# riffle-proto-grove-1_3.net
KiCad netlist of a schematic drawn in EAGLE
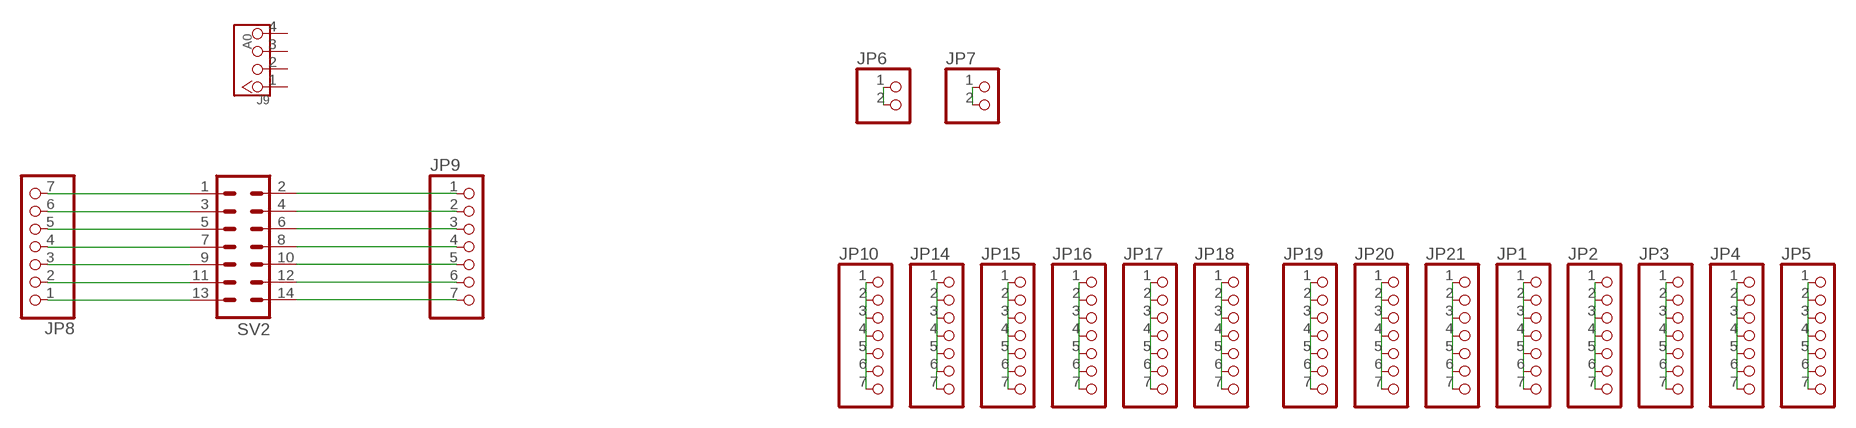
[diagram p0: schematic, sheet 1]

(export (version "E")
  (design (tool "Eeschema 10.0.6"))
  (components
    (comp (ref "J9")
      (value "A0")
      (footprint "eagle-import:4P-2.0-90D")
      (libsource (lib "eagle-import") (part "TWIG-4P-2.0'90D'"))
    )
    (comp (ref "JP1")
      (value "HEADER-1X770MIL")
      (footprint "eagle-import:1X07_ROUND_70")
      (libsource (lib "eagle-import") (part "HEADER-1X770MIL"))
    )
    (comp (ref "JP2")
      (value "HEADER-1X770MIL")
      (footprint "eagle-import:1X07_ROUND_70")
      (libsource (lib "eagle-import") (part "HEADER-1X770MIL"))
    )
    (comp (ref "JP3")
      (value "HEADER-1X770MIL")
      (footprint "eagle-import:1X07_ROUND_70")
      (libsource (lib "eagle-import") (part "HEADER-1X770MIL"))
    )
    (comp (ref "JP4")
      (value "HEADER-1X770MIL")
      (footprint "eagle-import:1X07_ROUND_70")
      (libsource (lib "eagle-import") (part "HEADER-1X770MIL"))
    )
    (comp (ref "JP5")
      (value "HEADER-1X770MIL")
      (footprint "eagle-import:1X07_ROUND_70")
      (libsource (lib "eagle-import") (part "HEADER-1X770MIL"))
    )
    (comp (ref "JP6")
      (value "HEADER-1X2ROUND")
      (footprint "eagle-import:1X02_ROUND")
      (libsource (lib "eagle-import") (part "HEADER-1X2ROUND"))
    )
    (comp (ref "JP7")
      (value "HEADER-1X2ROUND")
      (footprint "eagle-import:1X02_ROUND")
      (libsource (lib "eagle-import") (part "HEADER-1X2ROUND"))
    )
    (comp (ref "JP8")
      (value "HEADER-1X770MIL")
      (footprint "eagle-import:1X07_ROUND_70")
      (libsource (lib "eagle-import") (part "HEADER-1X770MIL"))
    )
    (comp (ref "JP9")
      (value "HEADER-1X770MIL")
      (footprint "eagle-import:1X07_ROUND_70")
      (libsource (lib "eagle-import") (part "HEADER-1X770MIL"))
    )
    (comp (ref "JP10")
      (value "HEADER-1X770MIL")
      (footprint "eagle-import:1X07_ROUND_70")
      (libsource (lib "eagle-import") (part "HEADER-1X770MIL"))
    )
    (comp (ref "JP14")
      (value "HEADER-1X770MIL")
      (footprint "eagle-import:1X07_ROUND_70")
      (libsource (lib "eagle-import") (part "HEADER-1X770MIL"))
    )
    (comp (ref "JP15")
      (value "HEADER-1X770MIL")
      (footprint "eagle-import:1X07_ROUND_70")
      (libsource (lib "eagle-import") (part "HEADER-1X770MIL"))
    )
    (comp (ref "JP16")
      (value "HEADER-1X770MIL")
      (footprint "eagle-import:1X07_ROUND_70")
      (libsource (lib "eagle-import") (part "HEADER-1X770MIL"))
    )
    (comp (ref "JP17")
      (value "HEADER-1X770MIL")
      (footprint "eagle-import:1X07_ROUND_70")
      (libsource (lib "eagle-import") (part "HEADER-1X770MIL"))
    )
    (comp (ref "JP18")
      (value "HEADER-1X770MIL")
      (footprint "eagle-import:1X07_ROUND_70")
      (libsource (lib "eagle-import") (part "HEADER-1X770MIL"))
    )
    (comp (ref "JP19")
      (value "HEADER-1X770MIL")
      (footprint "eagle-import:1X07_ROUND_70")
      (libsource (lib "eagle-import") (part "HEADER-1X770MIL"))
    )
    (comp (ref "JP20")
      (value "HEADER-1X770MIL")
      (footprint "eagle-import:1X07_ROUND_70")
      (libsource (lib "eagle-import") (part "HEADER-1X770MIL"))
    )
    (comp (ref "JP21")
      (value "HEADER-1X770MIL")
      (footprint "eagle-import:1X07_ROUND_70")
      (libsource (lib "eagle-import") (part "HEADER-1X770MIL"))
    )
    (comp (ref "SV2")
      (value "MA07-2")
      (footprint "eagle-import:MA07-2")
      (libsource (lib "eagle-import") (part "MA07-2"))
    )
  )
  (nets
    (net (code "1") (name "Net-(JP1-Pad1)") (class "Default")
      (node (ref "JP1") (pin "1") (pinfunction "1_1") (pintype "passive"))
      (node (ref "JP1") (pin "2") (pinfunction "2_2") (pintype "passive"))
      (node (ref "JP1") (pin "3") (pinfunction "3_3") (pintype "passive"))
      (node (ref "JP1") (pin "4") (pinfunction "4_4") (pintype "passive"))
      (node (ref "JP1") (pin "5") (pinfunction "5_5") (pintype "passive"))
      (node (ref "JP1") (pin "6") (pinfunction "6_6") (pintype "passive"))
      (node (ref "JP1") (pin "7") (pinfunction "7_7") (pintype "passive"))
    )
    (net (code "2") (name "Net-(JP2-Pad1)") (class "Default")
      (node (ref "JP2") (pin "1") (pinfunction "1_1") (pintype "passive"))
      (node (ref "JP2") (pin "2") (pinfunction "2_2") (pintype "passive"))
      (node (ref "JP2") (pin "3") (pinfunction "3_3") (pintype "passive"))
      (node (ref "JP2") (pin "4") (pinfunction "4_4") (pintype "passive"))
      (node (ref "JP2") (pin "5") (pinfunction "5_5") (pintype "passive"))
      (node (ref "JP2") (pin "6") (pinfunction "6_6") (pintype "passive"))
      (node (ref "JP2") (pin "7") (pinfunction "7_7") (pintype "passive"))
    )
    (net (code "3") (name "Net-(JP3-Pad1)") (class "Default")
      (node (ref "JP3") (pin "1") (pinfunction "1_1") (pintype "passive"))
      (node (ref "JP3") (pin "2") (pinfunction "2_2") (pintype "passive"))
      (node (ref "JP3") (pin "3") (pinfunction "3_3") (pintype "passive"))
      (node (ref "JP3") (pin "4") (pinfunction "4_4") (pintype "passive"))
      (node (ref "JP3") (pin "5") (pinfunction "5_5") (pintype "passive"))
      (node (ref "JP3") (pin "6") (pinfunction "6_6") (pintype "passive"))
      (node (ref "JP3") (pin "7") (pinfunction "7_7") (pintype "passive"))
    )
    (net (code "4") (name "Net-(JP4-Pad1)") (class "Default")
      (node (ref "JP4") (pin "1") (pinfunction "1_1") (pintype "passive"))
      (node (ref "JP4") (pin "2") (pinfunction "2_2") (pintype "passive"))
      (node (ref "JP4") (pin "3") (pinfunction "3_3") (pintype "passive"))
      (node (ref "JP4") (pin "4") (pinfunction "4_4") (pintype "passive"))
      (node (ref "JP4") (pin "5") (pinfunction "5_5") (pintype "passive"))
      (node (ref "JP4") (pin "6") (pinfunction "6_6") (pintype "passive"))
      (node (ref "JP4") (pin "7") (pinfunction "7_7") (pintype "passive"))
    )
    (net (code "5") (name "Net-(JP5-Pad1)") (class "Default")
      (node (ref "JP5") (pin "1") (pinfunction "1_1") (pintype "passive"))
      (node (ref "JP5") (pin "2") (pinfunction "2_2") (pintype "passive"))
      (node (ref "JP5") (pin "3") (pinfunction "3_3") (pintype "passive"))
      (node (ref "JP5") (pin "4") (pinfunction "4_4") (pintype "passive"))
      (node (ref "JP5") (pin "5") (pinfunction "5_5") (pintype "passive"))
      (node (ref "JP5") (pin "6") (pinfunction "6_6") (pintype "passive"))
      (node (ref "JP5") (pin "7") (pinfunction "7_7") (pintype "passive"))
    )
    (net (code "6") (name "Net-(JP6-Pad1)") (class "Default")
      (node (ref "JP6") (pin "1") (pinfunction "1_1") (pintype "passive"))
      (node (ref "JP6") (pin "2") (pinfunction "2_2") (pintype "passive"))
    )
    (net (code "7") (name "Net-(JP7-Pad1)") (class "Default")
      (node (ref "JP7") (pin "1") (pinfunction "1_1") (pintype "passive"))
      (node (ref "JP7") (pin "2") (pinfunction "2_2") (pintype "passive"))
    )
    (net (code "8") (name "Net-(JP8-Pad1)") (class "Default")
      (node (ref "JP8") (pin "1") (pinfunction "1_1") (pintype "passive"))
      (node (ref "SV2") (pin "13") (pinfunction "13_13") (pintype "passive"))
    )
    (net (code "9") (name "Net-(JP8-Pad2)") (class "Default")
      (node (ref "JP8") (pin "2") (pinfunction "2_2") (pintype "passive"))
      (node (ref "SV2") (pin "11") (pinfunction "11_11") (pintype "passive"))
    )
    (net (code "10") (name "Net-(JP8-Pad3)") (class "Default")
      (node (ref "JP8") (pin "3") (pinfunction "3_3") (pintype "passive"))
      (node (ref "SV2") (pin "9") (pinfunction "9_9") (pintype "passive"))
    )
    (net (code "11") (name "Net-(JP8-Pad4)") (class "Default")
      (node (ref "JP8") (pin "4") (pinfunction "4_4") (pintype "passive"))
      (node (ref "SV2") (pin "7") (pinfunction "7_7") (pintype "passive"))
    )
    (net (code "12") (name "Net-(JP8-Pad5)") (class "Default")
      (node (ref "JP8") (pin "5") (pinfunction "5_5") (pintype "passive"))
      (node (ref "SV2") (pin "5") (pinfunction "5_5") (pintype "passive"))
    )
    (net (code "13") (name "Net-(JP8-Pad6)") (class "Default")
      (node (ref "JP8") (pin "6") (pinfunction "6_6") (pintype "passive"))
      (node (ref "SV2") (pin "3") (pinfunction "3_3") (pintype "passive"))
    )
    (net (code "14") (name "Net-(JP8-Pad7)") (class "Default")
      (node (ref "JP8") (pin "7") (pinfunction "7_7") (pintype "passive"))
      (node (ref "SV2") (pin "1") (pinfunction "1_1") (pintype "passive"))
    )
    (net (code "15") (name "Net-(JP9-Pad1)") (class "Default")
      (node (ref "JP9") (pin "1") (pinfunction "1_1") (pintype "passive"))
      (node (ref "SV2") (pin "2") (pinfunction "2_2") (pintype "passive"))
    )
    (net (code "16") (name "Net-(JP9-Pad2)") (class "Default")
      (node (ref "JP9") (pin "2") (pinfunction "2_2") (pintype "passive"))
      (node (ref "SV2") (pin "4") (pinfunction "4_4") (pintype "passive"))
    )
    (net (code "17") (name "Net-(JP9-Pad3)") (class "Default")
      (node (ref "JP9") (pin "3") (pinfunction "3_3") (pintype "passive"))
      (node (ref "SV2") (pin "6") (pinfunction "6_6") (pintype "passive"))
    )
    (net (code "18") (name "Net-(JP9-Pad4)") (class "Default")
      (node (ref "JP9") (pin "4") (pinfunction "4_4") (pintype "passive"))
      (node (ref "SV2") (pin "8") (pinfunction "8_8") (pintype "passive"))
    )
    (net (code "19") (name "Net-(JP9-Pad5)") (class "Default")
      (node (ref "JP9") (pin "5") (pinfunction "5_5") (pintype "passive"))
      (node (ref "SV2") (pin "10") (pinfunction "10_10") (pintype "passive"))
    )
    (net (code "20") (name "Net-(JP9-Pad6)") (class "Default")
      (node (ref "JP9") (pin "6") (pinfunction "6_6") (pintype "passive"))
      (node (ref "SV2") (pin "12") (pinfunction "12_12") (pintype "passive"))
    )
    (net (code "21") (name "Net-(JP9-Pad7)") (class "Default")
      (node (ref "JP9") (pin "7") (pinfunction "7_7") (pintype "passive"))
      (node (ref "SV2") (pin "14") (pinfunction "14_14") (pintype "passive"))
    )
    (net (code "22") (name "Net-(JP10-Pad1)") (class "Default")
      (node (ref "JP10") (pin "1") (pinfunction "1_1") (pintype "passive"))
      (node (ref "JP10") (pin "2") (pinfunction "2_2") (pintype "passive"))
      (node (ref "JP10") (pin "3") (pinfunction "3_3") (pintype "passive"))
      (node (ref "JP10") (pin "4") (pinfunction "4_4") (pintype "passive"))
      (node (ref "JP10") (pin "5") (pinfunction "5_5") (pintype "passive"))
      (node (ref "JP10") (pin "6") (pinfunction "6_6") (pintype "passive"))
      (node (ref "JP10") (pin "7") (pinfunction "7_7") (pintype "passive"))
    )
    (net (code "23") (name "Net-(JP14-Pad1)") (class "Default")
      (node (ref "JP14") (pin "1") (pinfunction "1_1") (pintype "passive"))
      (node (ref "JP14") (pin "2") (pinfunction "2_2") (pintype "passive"))
      (node (ref "JP14") (pin "3") (pinfunction "3_3") (pintype "passive"))
      (node (ref "JP14") (pin "4") (pinfunction "4_4") (pintype "passive"))
      (node (ref "JP14") (pin "5") (pinfunction "5_5") (pintype "passive"))
      (node (ref "JP14") (pin "6") (pinfunction "6_6") (pintype "passive"))
      (node (ref "JP14") (pin "7") (pinfunction "7_7") (pintype "passive"))
    )
    (net (code "24") (name "Net-(JP15-Pad1)") (class "Default")
      (node (ref "JP15") (pin "1") (pinfunction "1_1") (pintype "passive"))
      (node (ref "JP15") (pin "2") (pinfunction "2_2") (pintype "passive"))
      (node (ref "JP15") (pin "3") (pinfunction "3_3") (pintype "passive"))
      (node (ref "JP15") (pin "4") (pinfunction "4_4") (pintype "passive"))
      (node (ref "JP15") (pin "5") (pinfunction "5_5") (pintype "passive"))
      (node (ref "JP15") (pin "6") (pinfunction "6_6") (pintype "passive"))
      (node (ref "JP15") (pin "7") (pinfunction "7_7") (pintype "passive"))
    )
    (net (code "25") (name "Net-(JP16-Pad1)") (class "Default")
      (node (ref "JP16") (pin "1") (pinfunction "1_1") (pintype "passive"))
      (node (ref "JP16") (pin "2") (pinfunction "2_2") (pintype "passive"))
      (node (ref "JP16") (pin "3") (pinfunction "3_3") (pintype "passive"))
      (node (ref "JP16") (pin "4") (pinfunction "4_4") (pintype "passive"))
      (node (ref "JP16") (pin "5") (pinfunction "5_5") (pintype "passive"))
      (node (ref "JP16") (pin "6") (pinfunction "6_6") (pintype "passive"))
      (node (ref "JP16") (pin "7") (pinfunction "7_7") (pintype "passive"))
    )
    (net (code "26") (name "Net-(JP17-Pad1)") (class "Default")
      (node (ref "JP17") (pin "1") (pinfunction "1_1") (pintype "passive"))
      (node (ref "JP17") (pin "2") (pinfunction "2_2") (pintype "passive"))
      (node (ref "JP17") (pin "3") (pinfunction "3_3") (pintype "passive"))
      (node (ref "JP17") (pin "4") (pinfunction "4_4") (pintype "passive"))
      (node (ref "JP17") (pin "5") (pinfunction "5_5") (pintype "passive"))
      (node (ref "JP17") (pin "6") (pinfunction "6_6") (pintype "passive"))
      (node (ref "JP17") (pin "7") (pinfunction "7_7") (pintype "passive"))
    )
    (net (code "27") (name "Net-(JP18-Pad1)") (class "Default")
      (node (ref "JP18") (pin "1") (pinfunction "1_1") (pintype "passive"))
      (node (ref "JP18") (pin "2") (pinfunction "2_2") (pintype "passive"))
      (node (ref "JP18") (pin "3") (pinfunction "3_3") (pintype "passive"))
      (node (ref "JP18") (pin "4") (pinfunction "4_4") (pintype "passive"))
      (node (ref "JP18") (pin "5") (pinfunction "5_5") (pintype "passive"))
      (node (ref "JP18") (pin "6") (pinfunction "6_6") (pintype "passive"))
      (node (ref "JP18") (pin "7") (pinfunction "7_7") (pintype "passive"))
    )
    (net (code "28") (name "Net-(JP19-Pad1)") (class "Default")
      (node (ref "JP19") (pin "1") (pinfunction "1_1") (pintype "passive"))
      (node (ref "JP19") (pin "2") (pinfunction "2_2") (pintype "passive"))
      (node (ref "JP19") (pin "3") (pinfunction "3_3") (pintype "passive"))
      (node (ref "JP19") (pin "4") (pinfunction "4_4") (pintype "passive"))
      (node (ref "JP19") (pin "5") (pinfunction "5_5") (pintype "passive"))
      (node (ref "JP19") (pin "6") (pinfunction "6_6") (pintype "passive"))
      (node (ref "JP19") (pin "7") (pinfunction "7_7") (pintype "passive"))
    )
    (net (code "29") (name "Net-(JP20-Pad1)") (class "Default")
      (node (ref "JP20") (pin "1") (pinfunction "1_1") (pintype "passive"))
      (node (ref "JP20") (pin "2") (pinfunction "2_2") (pintype "passive"))
      (node (ref "JP20") (pin "3") (pinfunction "3_3") (pintype "passive"))
      (node (ref "JP20") (pin "4") (pinfunction "4_4") (pintype "passive"))
      (node (ref "JP20") (pin "5") (pinfunction "5_5") (pintype "passive"))
      (node (ref "JP20") (pin "6") (pinfunction "6_6") (pintype "passive"))
      (node (ref "JP20") (pin "7") (pinfunction "7_7") (pintype "passive"))
    )
    (net (code "30") (name "Net-(JP21-Pad1)") (class "Default")
      (node (ref "JP21") (pin "1") (pinfunction "1_1") (pintype "passive"))
      (node (ref "JP21") (pin "2") (pinfunction "2_2") (pintype "passive"))
      (node (ref "JP21") (pin "3") (pinfunction "3_3") (pintype "passive"))
      (node (ref "JP21") (pin "4") (pinfunction "4_4") (pintype "passive"))
      (node (ref "JP21") (pin "5") (pinfunction "5_5") (pintype "passive"))
      (node (ref "JP21") (pin "6") (pinfunction "6_6") (pintype "passive"))
      (node (ref "JP21") (pin "7") (pinfunction "7_7") (pintype "passive"))
    )
    (net (code "31") (name "unconnected-(J9-Pad1)") (class "Default")
      (node (ref "J9") (pin "1") (pinfunction "1_1") (pintype "bidirectional"))
    )
    (net (code "32") (name "unconnected-(J9-Pad2)") (class "Default")
      (node (ref "J9") (pin "2") (pinfunction "2_2") (pintype "bidirectional"))
    )
    (net (code "33") (name "unconnected-(J9-Pad3)") (class "Default")
      (node (ref "J9") (pin "3") (pinfunction "3_3") (pintype "bidirectional"))
    )
    (net (code "34") (name "unconnected-(J9-Pad4)") (class "Default")
      (node (ref "J9") (pin "4") (pinfunction "4_4") (pintype "bidirectional"))
    )
  )
)
